# XX-Piezo-Receiver.net
KiCad netlist of a schematic drawn in EAGLE
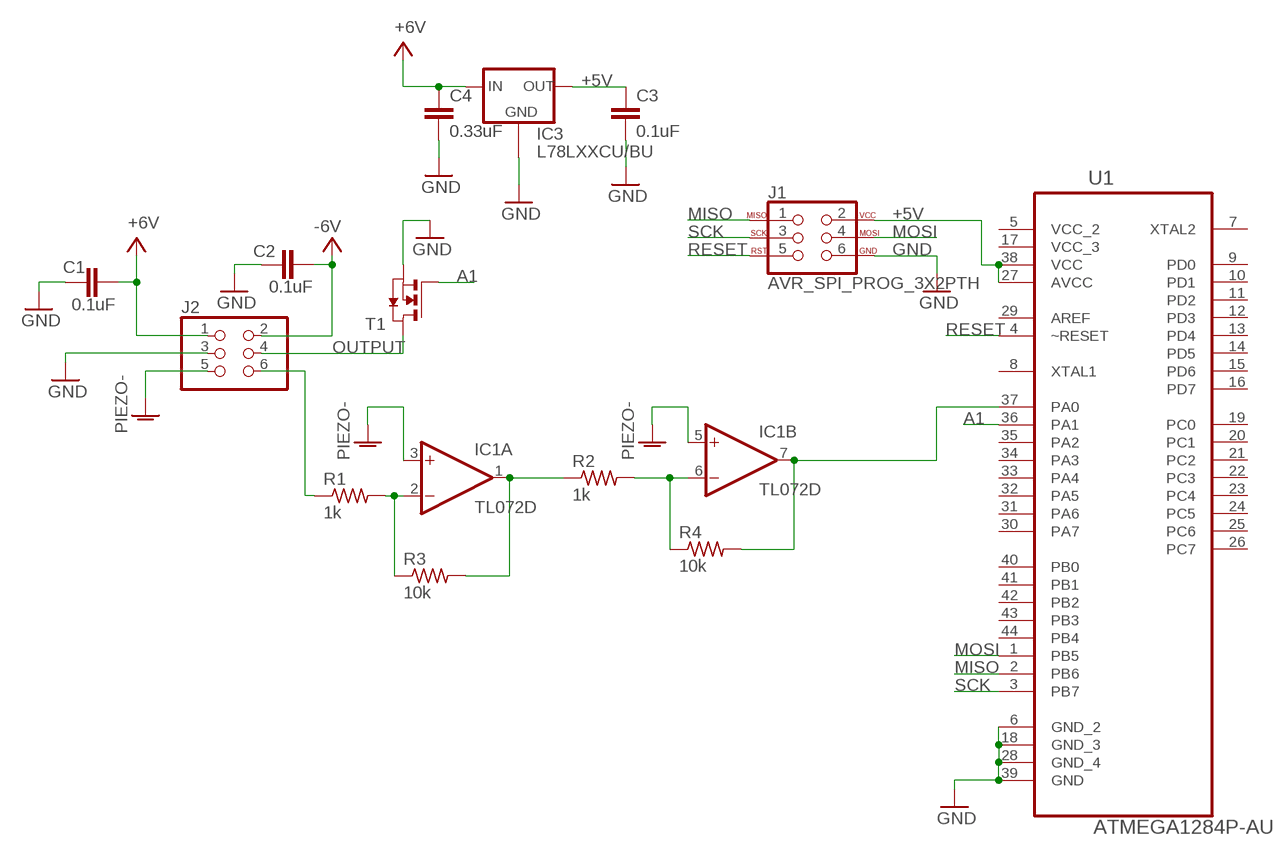
[diagram p0: schematic, sheet 1]

(export (version "E")
  (design (tool "Eeschema 10.0.6"))
  (components
    (comp (ref "C1")
      (value "0.1uF")
      (footprint "eagle-import:C0603")
      (libsource (lib "eagle-import") (part "C-EUC0603"))
    )
    (comp (ref "C2")
      (value "0.1uF")
      (footprint "eagle-import:C0603")
      (libsource (lib "eagle-import") (part "C-EUC0603"))
    )
    (comp (ref "C3")
      (value "0.1uF")
      (footprint "eagle-import:C0603")
      (libsource (lib "eagle-import") (part "C-EUC0603"))
    )
    (comp (ref "C4")
      (value "0.33uF")
      (footprint "eagle-import:C0603")
      (libsource (lib "eagle-import") (part "C-EUC0603"))
    )
    (comp (ref "IC1")
      (value "TL072D")
      (footprint "eagle-import:SO08")
      (libsource (lib "eagle-import") (part "TL072D"))
    )
    (comp (ref "IC3")
      (value "L78LXXCU/BU")
      (footprint "eagle-import:SOT89")
      (libsource (lib "eagle-import") (part "L78LXXCU/BU"))
    )
    (comp (ref "J1")
      (value "AVR_SPI_PROG_3X2PTH")
      (footprint "eagle-import:2X3")
      (libsource (lib "eagle-import") (part "AVR_SPI_PROG_3X2PTH"))
    )
    (comp (ref "J2")
      (value "PINHD-2X3")
      (footprint "eagle-import:2X03")
      (libsource (lib "eagle-import") (part "PINHD-2X3"))
    )
    (comp (ref "R1")
      (value "1k")
      (footprint "eagle-import:R0603")
      (libsource (lib "eagle-import") (part "R-US_R0603"))
    )
    (comp (ref "R2")
      (value "1k")
      (footprint "eagle-import:R0603")
      (libsource (lib "eagle-import") (part "R-US_R0603"))
    )
    (comp (ref "R3")
      (value "10k")
      (footprint "eagle-import:R0603")
      (libsource (lib "eagle-import") (part "R-US_R0603"))
    )
    (comp (ref "R4")
      (value "10k")
      (footprint "eagle-import:R0603")
      (libsource (lib "eagle-import") (part "R-US_R0603"))
    )
    (comp (ref "T1")
      (value "NMOSSOT23")
      (footprint "eagle-import:SOT-23")
      (libsource (lib "eagle-import") (part "NMOSSOT23"))
    )
    (comp (ref "U1")
      (value "ATMEGA1284P-AU")
      (footprint "eagle-import:QFP80P1200X1200X120-44N")
      (libsource (lib "eagle-import") (part "ATMEGA1284P-AU"))
    )
  )
  (nets
    (net (code "1") (name "+6V") (class "Default")
      (node (ref "C1") (pin "2") (pinfunction "2_2") (pintype "passive"))
      (node (ref "C4") (pin "1") (pinfunction "1_1") (pintype "passive"))
      (node (ref "IC3") (pin "3") (pinfunction "IN_3") (pintype "input"))
      (node (ref "J2") (pin "1") (pinfunction "1_1") (pintype "passive"))
    )
    (net (code "2") (name "-6V") (class "Default")
      (node (ref "C2") (pin "2") (pinfunction "2_2") (pintype "passive"))
      (node (ref "J2") (pin "2") (pinfunction "2_2") (pintype "passive"))
    )
    (net (code "3") (name "/+5V") (class "Default")
      (node (ref "C3") (pin "1") (pinfunction "1_1") (pintype "passive"))
      (node (ref "IC3") (pin "1") (pinfunction "OUT_1") (pintype "passive"))
      (node (ref "J1") (pin "2") (pinfunction "2_2") (pintype "passive"))
      (node (ref "U1") (pin "27") (pinfunction "AVCC_27") (pintype "power_in"))
      (node (ref "U1") (pin "38") (pinfunction "VCC_38") (pintype "power_in"))
    )
    (net (code "4") (name "/A1") (class "Default")
      (node (ref "T1") (pin "3") (pinfunction "G_3") (pintype "passive"))
      (node (ref "U1") (pin "36") (pinfunction "PA1_36") (pintype "bidirectional"))
    )
    (net (code "5") (name "/MISO") (class "Default")
      (node (ref "J1") (pin "1") (pinfunction "1_1") (pintype "passive"))
      (node (ref "U1") (pin "2") (pinfunction "PB6_2") (pintype "bidirectional"))
    )
    (net (code "6") (name "/MOSI") (class "Default")
      (node (ref "J1") (pin "4") (pinfunction "4_4") (pintype "passive"))
      (node (ref "U1") (pin "1") (pinfunction "PB5_1") (pintype "bidirectional"))
    )
    (net (code "7") (name "/OUTPUT") (class "Default")
      (node (ref "J2") (pin "4") (pinfunction "4_4") (pintype "passive"))
      (node (ref "T1") (pin "1") (pinfunction "D_1") (pintype "passive"))
    )
    (net (code "8") (name "/RESET") (class "Default")
      (node (ref "J1") (pin "5") (pinfunction "5_5") (pintype "passive"))
      (node (ref "U1") (pin "4") (pinfunction "~{RESET}_4") (pintype "input"))
    )
    (net (code "9") (name "/SCK") (class "Default")
      (node (ref "J1") (pin "3") (pinfunction "3_3") (pintype "passive"))
      (node (ref "U1") (pin "3") (pinfunction "PB7_3") (pintype "bidirectional"))
    )
    (net (code "10") (name "/VCC_2") (class "Default")
      (node (ref "U1") (pin "5") (pinfunction "VCC_2_5") (pintype "power_in"))
    )
    (net (code "11") (name "/VCC_3") (class "Default")
      (node (ref "U1") (pin "17") (pinfunction "VCC_3_17") (pintype "power_in"))
    )
    (net (code "12") (name "GND") (class "Default")
      (node (ref "C1") (pin "1") (pinfunction "1_1") (pintype "passive"))
      (node (ref "C2") (pin "1") (pinfunction "1_1") (pintype "passive"))
      (node (ref "C3") (pin "2") (pinfunction "2_2") (pintype "passive"))
      (node (ref "C4") (pin "2") (pinfunction "2_2") (pintype "passive"))
      (node (ref "IC3") (pin "4") (pinfunction "GND1_4") (pintype "input"))
      (node (ref "J1") (pin "6") (pinfunction "6_6") (pintype "passive"))
      (node (ref "J2") (pin "3") (pinfunction "3_3") (pintype "passive"))
      (node (ref "T1") (pin "2") (pinfunction "S_2") (pintype "passive"))
      (node (ref "U1") (pin "18") (pinfunction "GND_3_18") (pintype "passive"))
      (node (ref "U1") (pin "28") (pinfunction "GND_4_28") (pintype "passive"))
      (node (ref "U1") (pin "39") (pinfunction "GND_39") (pintype "passive"))
      (node (ref "U1") (pin "6") (pinfunction "GND_2_6") (pintype "passive"))
    )
    (net (code "13") (name "Net-(IC1A--IN)") (class "Default")
      (node (ref "IC1") (pin "2") (pinfunction "-IN_2") (pintype "input"))
      (node (ref "R1") (pin "2") (pinfunction "2_2") (pintype "passive"))
      (node (ref "R3") (pin "1") (pinfunction "1_1") (pintype "passive"))
    )
    (net (code "14") (name "Net-(IC1A-OUT)") (class "Default")
      (node (ref "IC1") (pin "1") (pinfunction "OUT_1") (pintype "output"))
      (node (ref "R2") (pin "1") (pinfunction "1_1") (pintype "passive"))
      (node (ref "R3") (pin "2") (pinfunction "2_2") (pintype "passive"))
    )
    (net (code "15") (name "Net-(IC1B--IN)") (class "Default")
      (node (ref "IC1") (pin "6") (pinfunction "-IN_6") (pintype "input"))
      (node (ref "R2") (pin "2") (pinfunction "2_2") (pintype "passive"))
      (node (ref "R4") (pin "1") (pinfunction "1_1") (pintype "passive"))
    )
    (net (code "16") (name "Net-(IC1B-OUT)") (class "Default")
      (node (ref "IC1") (pin "7") (pinfunction "OUT_7") (pintype "output"))
      (node (ref "R4") (pin "2") (pinfunction "2_2") (pintype "passive"))
      (node (ref "U1") (pin "37") (pinfunction "PA0_37") (pintype "bidirectional"))
    )
    (net (code "17") (name "Net-(J2-Pad6)") (class "Default")
      (node (ref "J2") (pin "6") (pinfunction "6_6") (pintype "passive"))
      (node (ref "R1") (pin "1") (pinfunction "1_1") (pintype "passive"))
    )
    (net (code "18") (name "PIEZO-") (class "Default")
      (node (ref "IC1") (pin "3") (pinfunction "+IN_3") (pintype "input"))
      (node (ref "IC1") (pin "5") (pinfunction "+IN_5") (pintype "input"))
      (node (ref "J2") (pin "5") (pinfunction "5_5") (pintype "passive"))
    )
    (net (code "19") (name "unconnected-(IC3-GND-Pad2)") (class "Default")
      (node (ref "IC3") (pin "2") (pinfunction "GND_2") (pintype "input"))
    )
    (net (code "20") (name "unconnected-(U1-AREF-Pad29)") (class "Default")
      (node (ref "U1") (pin "29") (pinfunction "AREF_29") (pintype "input"))
    )
    (net (code "21") (name "unconnected-(U1-PA2-Pad35)") (class "Default")
      (node (ref "U1") (pin "35") (pinfunction "PA2_35") (pintype "bidirectional"))
    )
    (net (code "22") (name "unconnected-(U1-PA3-Pad34)") (class "Default")
      (node (ref "U1") (pin "34") (pinfunction "PA3_34") (pintype "bidirectional"))
    )
    (net (code "23") (name "unconnected-(U1-PA4-Pad33)") (class "Default")
      (node (ref "U1") (pin "33") (pinfunction "PA4_33") (pintype "bidirectional"))
    )
    (net (code "24") (name "unconnected-(U1-PA5-Pad32)") (class "Default")
      (node (ref "U1") (pin "32") (pinfunction "PA5_32") (pintype "bidirectional"))
    )
    (net (code "25") (name "unconnected-(U1-PA6-Pad31)") (class "Default")
      (node (ref "U1") (pin "31") (pinfunction "PA6_31") (pintype "bidirectional"))
    )
    (net (code "26") (name "unconnected-(U1-PA7-Pad30)") (class "Default")
      (node (ref "U1") (pin "30") (pinfunction "PA7_30") (pintype "bidirectional"))
    )
    (net (code "27") (name "unconnected-(U1-PB0-Pad40)") (class "Default")
      (node (ref "U1") (pin "40") (pinfunction "PB0_40") (pintype "bidirectional"))
    )
    (net (code "28") (name "unconnected-(U1-PB1-Pad41)") (class "Default")
      (node (ref "U1") (pin "41") (pinfunction "PB1_41") (pintype "bidirectional"))
    )
    (net (code "29") (name "unconnected-(U1-PB2-Pad42)") (class "Default")
      (node (ref "U1") (pin "42") (pinfunction "PB2_42") (pintype "bidirectional"))
    )
    (net (code "30") (name "unconnected-(U1-PB3-Pad43)") (class "Default")
      (node (ref "U1") (pin "43") (pinfunction "PB3_43") (pintype "bidirectional"))
    )
    (net (code "31") (name "unconnected-(U1-PB4-Pad44)") (class "Default")
      (node (ref "U1") (pin "44") (pinfunction "PB4_44") (pintype "bidirectional"))
    )
    (net (code "32") (name "unconnected-(U1-PC0-Pad19)") (class "Default")
      (node (ref "U1") (pin "19") (pinfunction "PC0_19") (pintype "bidirectional"))
    )
    (net (code "33") (name "unconnected-(U1-PC1-Pad20)") (class "Default")
      (node (ref "U1") (pin "20") (pinfunction "PC1_20") (pintype "bidirectional"))
    )
    (net (code "34") (name "unconnected-(U1-PC2-Pad21)") (class "Default")
      (node (ref "U1") (pin "21") (pinfunction "PC2_21") (pintype "bidirectional"))
    )
    (net (code "35") (name "unconnected-(U1-PC3-Pad22)") (class "Default")
      (node (ref "U1") (pin "22") (pinfunction "PC3_22") (pintype "bidirectional"))
    )
    (net (code "36") (name "unconnected-(U1-PC4-Pad23)") (class "Default")
      (node (ref "U1") (pin "23") (pinfunction "PC4_23") (pintype "bidirectional"))
    )
    (net (code "37") (name "unconnected-(U1-PC5-Pad24)") (class "Default")
      (node (ref "U1") (pin "24") (pinfunction "PC5_24") (pintype "bidirectional"))
    )
    (net (code "38") (name "unconnected-(U1-PC6-Pad25)") (class "Default")
      (node (ref "U1") (pin "25") (pinfunction "PC6_25") (pintype "bidirectional"))
    )
    (net (code "39") (name "unconnected-(U1-PC7-Pad26)") (class "Default")
      (node (ref "U1") (pin "26") (pinfunction "PC7_26") (pintype "bidirectional"))
    )
    (net (code "40") (name "unconnected-(U1-PD0-Pad9)") (class "Default")
      (node (ref "U1") (pin "9") (pinfunction "PD0_9") (pintype "bidirectional"))
    )
    (net (code "41") (name "unconnected-(U1-PD1-Pad10)") (class "Default")
      (node (ref "U1") (pin "10") (pinfunction "PD1_10") (pintype "bidirectional"))
    )
    (net (code "42") (name "unconnected-(U1-PD2-Pad11)") (class "Default")
      (node (ref "U1") (pin "11") (pinfunction "PD2_11") (pintype "bidirectional"))
    )
    (net (code "43") (name "unconnected-(U1-PD3-Pad12)") (class "Default")
      (node (ref "U1") (pin "12") (pinfunction "PD3_12") (pintype "bidirectional"))
    )
    (net (code "44") (name "unconnected-(U1-PD4-Pad13)") (class "Default")
      (node (ref "U1") (pin "13") (pinfunction "PD4_13") (pintype "bidirectional"))
    )
    (net (code "45") (name "unconnected-(U1-PD5-Pad14)") (class "Default")
      (node (ref "U1") (pin "14") (pinfunction "PD5_14") (pintype "bidirectional"))
    )
    (net (code "46") (name "unconnected-(U1-PD6-Pad15)") (class "Default")
      (node (ref "U1") (pin "15") (pinfunction "PD6_15") (pintype "bidirectional"))
    )
    (net (code "47") (name "unconnected-(U1-PD7-Pad16)") (class "Default")
      (node (ref "U1") (pin "16") (pinfunction "PD7_16") (pintype "bidirectional"))
    )
    (net (code "48") (name "unconnected-(U1-XTAL1-Pad8)") (class "Default")
      (node (ref "U1") (pin "8") (pinfunction "XTAL1_8") (pintype "input"))
    )
    (net (code "49") (name "unconnected-(U1-XTAL2-Pad7)") (class "Default")
      (node (ref "U1") (pin "7") (pinfunction "XTAL2_7") (pintype "output"))
    )
  )
)
